# Ethernet.net
KiCad netlist of a schematic drawn in Altium Designer
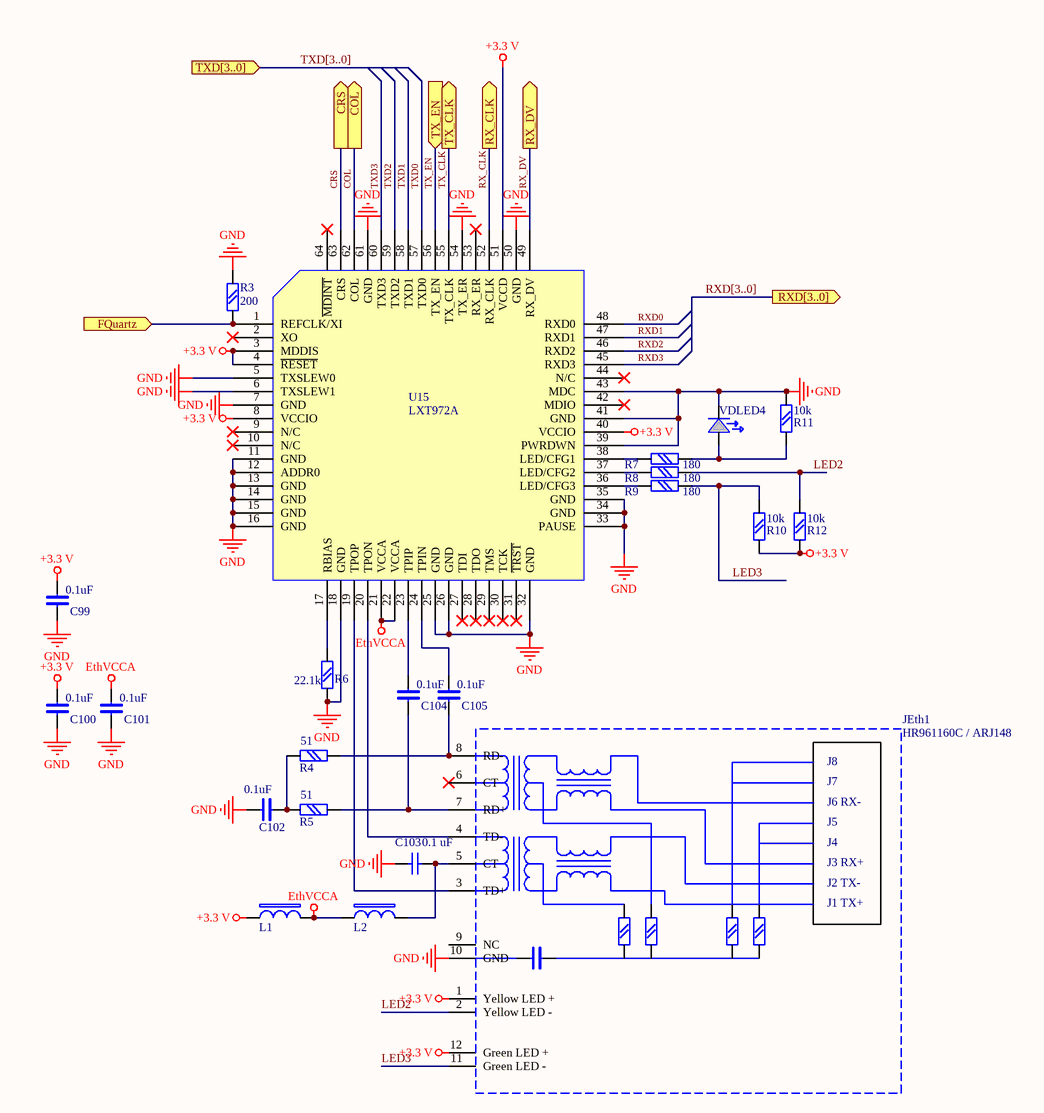
[diagram p0: Ethernet.SchDoc]

(export (version "E")
  (design (tool "Eeschema 10.0.6"))
  (components
    (comp (ref "C99") (value "0.1uF") (footprint "chip0603") (libsource (lib "vDevice") (part "C")))
    (comp (ref "C100") (value "0.1uF") (footprint "chip0603") (libsource (lib "vDevice") (part "C")))
    (comp (ref "C101") (value "0.1uF") (footprint "chip0603") (libsource (lib "vDevice") (part "C")))
    (comp (ref "C102") (value "0.1uF") (footprint "chip0603") (libsource (lib "vDevice") (part "C")))
    (comp (ref "C103")
      (value "0.1 uF")
      (footprint "chip0603")
      (description "Capacitor")
      (fields (field (name "Comment") "0.1uF") (field (name "PUBLISHER") "Altium Limited"))
      (libsource (lib "vDevice") (part "Cap"))
    )
    (comp (ref "C104") (value "0.1uF") (footprint "chip0603") (libsource (lib "vDevice") (part "C")))
    (comp (ref "C105") (value "0.1uF") (footprint "chip0603") (libsource (lib "vDevice") (part "C")))
    (comp (ref "JEth1")
      (value "HR961160C / ARJ148")
      (footprint "HR961160C")
      (libsource (lib "Backup of Mylib") (part "HR961160C"))
    )
    (comp (ref "L1") (value "DR") (footprint "chip0805") (libsource (lib "vDevice") (part "DR")))
    (comp (ref "L2") (value "DR") (footprint "chip0805") (libsource (lib "vDevice") (part "DR")))
    (comp (ref "R3") (value "200") (footprint "chip0603") (libsource (lib "vDevice") (part "R")))
    (comp (ref "R4") (value "51") (footprint "chip0603") (libsource (lib "vDevice") (part "R")))
    (comp (ref "R5") (value "51") (footprint "chip0603") (libsource (lib "vDevice") (part "R")))
    (comp (ref "R6") (value "22.1k") (footprint "chip0603") (libsource (lib "vDevice") (part "R")))
    (comp (ref "R7") (value "180") (footprint "chip0603") (libsource (lib "vDevice") (part "R")))
    (comp (ref "R8") (value "180") (footprint "chip0603") (libsource (lib "vDevice") (part "R")))
    (comp (ref "R9") (value "180") (footprint "chip0603") (libsource (lib "vDevice") (part "R")))
    (comp (ref "R10") (value "10k") (footprint "chip0603") (libsource (lib "vDevice") (part "R")))
    (comp (ref "R11") (value "10k") (footprint "chip0603") (libsource (lib "vDevice") (part "R")))
    (comp (ref "R12") (value "10k") (footprint "chip0603") (libsource (lib "vDevice") (part "R")))
    (comp (ref "U15")
      (value "LXT972A")
      (footprint "TQFP64")
      (libsource (lib "Backup of Mylib") (part "LXT972A"))
    )
    (comp (ref "VDLED4") (value "LED") (footprint "LED2P5_H") (libsource (lib "*") (part "AL307")))
  )
  (nets
    (net (code "1") (name "+3.3 V") (class "Default")
      (node (ref "C100") (pin "2") (pinfunction "2_2") (pintype "passive"))
      (node (ref "C99") (pin "2") (pinfunction "2_2") (pintype "passive"))
      (node (ref "JEth1") (pin "1") (pinfunction "Yellow_LED_+_1") (pintype "passive"))
      (node (ref "JEth1") (pin "12") (pinfunction "Green_LED_+_12") (pintype "passive"))
      (node (ref "L1") (pin "1") (pinfunction "1_1") (pintype "passive"))
      (node (ref "R10") (pin "1") (pinfunction "1_1") (pintype "passive"))
      (node (ref "R12") (pin "1") (pinfunction "1_1") (pintype "passive"))
      (node (ref "U15") (pin "3") (pinfunction "MDDIS_3") (pintype "passive"))
      (node (ref "U15") (pin "4") (pinfunction "RESET_4") (pintype "passive"))
      (node (ref "U15") (pin "40") (pinfunction "VCCIO_40") (pintype "passive"))
      (node (ref "U15") (pin "51") (pinfunction "VCCD_51") (pintype "passive"))
      (node (ref "U15") (pin "8") (pinfunction "VCCIO_8") (pintype "passive"))
    )
    (net (code "2") (name "/COL") (class "Default")
      (node (ref "U15") (pin "62") (pinfunction "COL_62") (pintype "passive"))
    )
    (net (code "3") (name "/CRS") (class "Default")
      (node (ref "U15") (pin "63") (pinfunction "CRS_63") (pintype "passive"))
    )
    (net (code "4") (name "/FQuartz") (class "Default")
      (node (ref "R3") (pin "1") (pinfunction "1_1") (pintype "passive"))
      (node (ref "U15") (pin "1") (pinfunction "REFCLK/XI_1") (pintype "passive"))
    )
    (net (code "5") (name "/LED2") (class "Default")
      (node (ref "JEth1") (pin "2") (pinfunction "Yellow_LED_-_2") (pintype "passive"))
      (node (ref "R12") (pin "2") (pinfunction "2_2") (pintype "passive"))
      (node (ref "R8") (pin "2") (pinfunction "2_2") (pintype "passive"))
    )
    (net (code "6") (name "/LED3") (class "Default")
      (node (ref "JEth1") (pin "11") (pinfunction "Green_LED_-_11") (pintype "passive"))
      (node (ref "R10") (pin "2") (pinfunction "2_2") (pintype "passive"))
      (node (ref "R9") (pin "2") (pinfunction "2_2") (pintype "passive"))
    )
    (net (code "7") (name "/RXD0") (class "Default")
      (node (ref "U15") (pin "48") (pinfunction "RXD0_48") (pintype "passive"))
    )
    (net (code "8") (name "/RXD1") (class "Default")
      (node (ref "U15") (pin "47") (pinfunction "RXD1_47") (pintype "passive"))
    )
    (net (code "9") (name "/RXD2") (class "Default")
      (node (ref "U15") (pin "46") (pinfunction "RXD2_46") (pintype "passive"))
    )
    (net (code "10") (name "/RXD3") (class "Default")
      (node (ref "U15") (pin "45") (pinfunction "RXD3_45") (pintype "passive"))
    )
    (net (code "12") (name "/RX_CLK") (class "Default")
      (node (ref "U15") (pin "52") (pinfunction "RX_CLK_52") (pintype "passive"))
    )
    (net (code "13") (name "/RX_DV") (class "Default")
      (node (ref "U15") (pin "49") (pinfunction "RX_DV_49") (pintype "passive"))
    )
    (net (code "14") (name "/TXD0") (class "Default")
      (node (ref "U15") (pin "57") (pinfunction "TXD0_57") (pintype "passive"))
    )
    (net (code "15") (name "/TXD1") (class "Default")
      (node (ref "U15") (pin "58") (pinfunction "TXD1_58") (pintype "passive"))
    )
    (net (code "16") (name "/TXD2") (class "Default")
      (node (ref "U15") (pin "59") (pinfunction "TXD2_59") (pintype "passive"))
    )
    (net (code "17") (name "/TXD3") (class "Default")
      (node (ref "U15") (pin "60") (pinfunction "TXD3_60") (pintype "passive"))
    )
    (net (code "19") (name "/TX_CLK") (class "Default")
      (node (ref "U15") (pin "55") (pinfunction "TX_CLK_55") (pintype "passive"))
    )
    (net (code "20") (name "/TX_EN") (class "Default")
      (node (ref "U15") (pin "56") (pinfunction "TX_EN_56") (pintype "passive"))
    )
    (net (code "21") (name "EthVCCA") (class "Default")
      (node (ref "C101") (pin "2") (pinfunction "2_2") (pintype "passive"))
      (node (ref "L1") (pin "2") (pinfunction "2_2") (pintype "passive"))
      (node (ref "L2") (pin "1") (pinfunction "1_1") (pintype "passive"))
      (node (ref "U15") (pin "21") (pinfunction "VCCA_21") (pintype "passive"))
      (node (ref "U15") (pin "22") (pinfunction "VCCA_22") (pintype "passive"))
    )
    (net (code "22") (name "GND") (class "Default")
      (node (ref "C100") (pin "1") (pinfunction "1_1") (pintype "passive"))
      (node (ref "C101") (pin "1") (pinfunction "1_1") (pintype "passive"))
      (node (ref "C102") (pin "2") (pinfunction "2_2") (pintype "passive"))
      (node (ref "C103") (pin "1") (pinfunction "1_1") (pintype "passive"))
      (node (ref "C99") (pin "1") (pinfunction "1_1") (pintype "passive"))
      (node (ref "JEth1") (pin "10") (pinfunction "GND_10") (pintype "power_in"))
      (node (ref "R11") (pin "2") (pinfunction "2_2") (pintype "passive"))
      (node (ref "R3") (pin "2") (pinfunction "2_2") (pintype "passive"))
      (node (ref "R6") (pin "2") (pinfunction "2_2") (pintype "passive"))
      (node (ref "U15") (pin "11") (pinfunction "GND_11") (pintype "passive"))
      (node (ref "U15") (pin "12") (pinfunction "ADDR0_12") (pintype "passive"))
      (node (ref "U15") (pin "13") (pinfunction "GND_13") (pintype "passive"))
      (node (ref "U15") (pin "14") (pinfunction "GND_14") (pintype "passive"))
      (node (ref "U15") (pin "15") (pinfunction "GND_15") (pintype "passive"))
      (node (ref "U15") (pin "16") (pinfunction "GND_16") (pintype "passive"))
      (node (ref "U15") (pin "18") (pinfunction "GND_18") (pintype "passive"))
      (node (ref "U15") (pin "25") (pinfunction "GND_25") (pintype "passive"))
      (node (ref "U15") (pin "26") (pinfunction "GND_26") (pintype "passive"))
      (node (ref "U15") (pin "32") (pinfunction "GND_32") (pintype "passive"))
      (node (ref "U15") (pin "33") (pinfunction "PAUSE_33") (pintype "passive"))
      (node (ref "U15") (pin "34") (pinfunction "GND_34") (pintype "passive"))
      (node (ref "U15") (pin "35") (pinfunction "GND_35") (pintype "passive"))
      (node (ref "U15") (pin "39") (pinfunction "PWRDWN_39") (pintype "passive"))
      (node (ref "U15") (pin "41") (pinfunction "GND_41") (pintype "passive"))
      (node (ref "U15") (pin "43") (pinfunction "MDC_43") (pintype "passive"))
      (node (ref "U15") (pin "5") (pinfunction "TXSLEW0_5") (pintype "passive"))
      (node (ref "U15") (pin "50") (pinfunction "GND_50") (pintype "passive"))
      (node (ref "U15") (pin "54") (pinfunction "TX_ER_54") (pintype "passive"))
      (node (ref "U15") (pin "6") (pinfunction "TXSLEW1_6") (pintype "passive"))
      (node (ref "U15") (pin "61") (pinfunction "GND_61") (pintype "passive"))
      (node (ref "U15") (pin "7") (pinfunction "GND_7") (pintype "passive"))
      (node (ref "VDLED4") (pin "CATH") (pinfunction "CATH_CATH") (pintype "passive"))
    )
    (net (code "23") (name "Net-(C102-Pad1)") (class "Default")
      (node (ref "C102") (pin "1") (pinfunction "1_1") (pintype "passive"))
      (node (ref "R4") (pin "1") (pinfunction "1_1") (pintype "passive"))
      (node (ref "R5") (pin "2") (pinfunction "2_2") (pintype "passive"))
    )
    (net (code "24") (name "Net-(C103-Pad2)") (class "Default")
      (node (ref "C103") (pin "2") (pinfunction "2_2") (pintype "passive"))
      (node (ref "JEth1") (pin "5") (pinfunction "CT_5") (pintype "passive"))
      (node (ref "L2") (pin "2") (pinfunction "2_2") (pintype "passive"))
    )
    (net (code "25") (name "Net-(JEth1-RD+)") (class "Default")
      (node (ref "C104") (pin "1") (pinfunction "1_1") (pintype "passive"))
      (node (ref "JEth1") (pin "7") (pinfunction "RD+_7") (pintype "passive"))
      (node (ref "R5") (pin "1") (pinfunction "1_1") (pintype "passive"))
    )
    (net (code "26") (name "Net-(JEth1-RD-)") (class "Default")
      (node (ref "C105") (pin "1") (pinfunction "1_1") (pintype "passive"))
      (node (ref "JEth1") (pin "8") (pinfunction "RD-_8") (pintype "passive"))
      (node (ref "R4") (pin "2") (pinfunction "2_2") (pintype "passive"))
    )
    (net (code "27") (name "Net-(JEth1-TD+)") (class "Default")
      (node (ref "JEth1") (pin "3") (pinfunction "TD+_3") (pintype "passive"))
      (node (ref "U15") (pin "19") (pinfunction "TPOP_19") (pintype "passive"))
    )
    (net (code "28") (name "Net-(JEth1-TD-)") (class "Default")
      (node (ref "JEth1") (pin "4") (pinfunction "TD-_4") (pintype "passive"))
      (node (ref "U15") (pin "20") (pinfunction "TPON_20") (pintype "passive"))
    )
    (net (code "29") (name "Net-(R11-Pad1)") (class "Default")
      (node (ref "R11") (pin "1") (pinfunction "1_1") (pintype "passive"))
      (node (ref "R7") (pin "2") (pinfunction "2_2") (pintype "passive"))
      (node (ref "VDLED4") (pin "ANOD") (pinfunction "ANOD_ANOD") (pintype "passive"))
    )
    (net (code "30") (name "Net-(U15-LED{slash}CFG1)") (class "Default")
      (node (ref "R7") (pin "1") (pinfunction "1_1") (pintype "passive"))
      (node (ref "U15") (pin "38") (pinfunction "LED/CFG1_38") (pintype "passive"))
    )
    (net (code "31") (name "Net-(U15-LED{slash}CFG2)") (class "Default")
      (node (ref "R8") (pin "1") (pinfunction "1_1") (pintype "passive"))
      (node (ref "U15") (pin "37") (pinfunction "LED/CFG2_37") (pintype "passive"))
    )
    (net (code "32") (name "Net-(U15-LED{slash}CFG3)") (class "Default")
      (node (ref "R9") (pin "1") (pinfunction "1_1") (pintype "passive"))
      (node (ref "U15") (pin "36") (pinfunction "LED/CFG3_36") (pintype "passive"))
    )
    (net (code "33") (name "Net-(U15-RBIAS)") (class "Default")
      (node (ref "R6") (pin "1") (pinfunction "1_1") (pintype "passive"))
      (node (ref "U15") (pin "17") (pinfunction "RBIAS_17") (pintype "passive"))
    )
    (net (code "34") (name "Net-(U15-TPIN)") (class "Default")
      (node (ref "C105") (pin "2") (pinfunction "2_2") (pintype "passive"))
      (node (ref "U15") (pin "24") (pinfunction "TPIN_24") (pintype "passive"))
    )
    (net (code "35") (name "Net-(U15-TPIP)") (class "Default")
      (node (ref "C104") (pin "2") (pinfunction "2_2") (pintype "passive"))
      (node (ref "U15") (pin "23") (pinfunction "TPIP_23") (pintype "passive"))
    )
    (net (code "36") (name "unconnected-(JEth1-CT-Pad6)") (class "Default")
      (node (ref "JEth1") (pin "6") (pinfunction "CT_6") (pintype "passive+no_connect"))
    )
    (net (code "37") (name "unconnected-(JEth1-NC-Pad9)") (class "Default")
      (node (ref "JEth1") (pin "9") (pinfunction "NC_9") (pintype "passive"))
    )
    (net (code "38") (name "unconnected-(JEth1-Pad1)") (class "Default")
      (node (ref "JEth1") (pin "1") (pinfunction "1_1") (pintype "passive"))
    )
    (net (code "39") (name "unconnected-(JEth1-Pad1)_1") (class "Default")
      (node (ref "JEth1") (pin "1") (pinfunction "1_1") (pintype "passive"))
    )
    (net (code "40") (name "unconnected-(JEth1-Pad1)_2") (class "Default")
      (node (ref "JEth1") (pin "1") (pinfunction "1_1") (pintype "passive"))
    )
    (net (code "41") (name "unconnected-(JEth1-Pad1)_3") (class "Default")
      (node (ref "JEth1") (pin "1") (pinfunction "1_1") (pintype "passive"))
    )
    (net (code "42") (name "unconnected-(JEth1-Pad1)_4") (class "Default")
      (node (ref "JEth1") (pin "1") (pinfunction "1_1") (pintype "passive"))
    )
    (net (code "43") (name "unconnected-(JEth1-Pad2)") (class "Default")
      (node (ref "JEth1") (pin "2") (pinfunction "2_2") (pintype "passive"))
    )
    (net (code "44") (name "unconnected-(JEth1-Pad2)_1") (class "Default")
      (node (ref "JEth1") (pin "2") (pinfunction "2_2") (pintype "passive"))
    )
    (net (code "45") (name "unconnected-(JEth1-Pad2)_2") (class "Default")
      (node (ref "JEth1") (pin "2") (pinfunction "2_2") (pintype "passive"))
    )
    (net (code "46") (name "unconnected-(JEth1-Pad2)_3") (class "Default")
      (node (ref "JEth1") (pin "2") (pinfunction "2_2") (pintype "passive"))
    )
    (net (code "47") (name "unconnected-(JEth1-Pad2)_4") (class "Default")
      (node (ref "JEth1") (pin "2") (pinfunction "2_2") (pintype "passive"))
    )
    (net (code "48") (name "unconnected-(U15-MDINT-Pad64)") (class "Default")
      (node (ref "U15") (pin "64") (pinfunction "MDINT_64") (pintype "passive+no_connect"))
    )
    (net (code "49") (name "unconnected-(U15-MDIO-Pad42)") (class "Default")
      (node (ref "U15") (pin "42") (pinfunction "MDIO_42") (pintype "passive+no_connect"))
    )
    (net (code "50") (name "unconnected-(U15-N{slash}C-Pad9)") (class "Default")
      (node (ref "U15") (pin "9") (pinfunction "N/C_9") (pintype "passive+no_connect"))
    )
    (net (code "51") (name "unconnected-(U15-N{slash}C-Pad10)") (class "Default")
      (node (ref "U15") (pin "10") (pinfunction "N/C_10") (pintype "passive+no_connect"))
    )
    (net (code "52") (name "unconnected-(U15-N{slash}C-Pad44)") (class "Default")
      (node (ref "U15") (pin "44") (pinfunction "N/C_44") (pintype "passive+no_connect"))
    )
    (net (code "53") (name "unconnected-(U15-RX_ER-Pad53)") (class "Default")
      (node (ref "U15") (pin "53") (pinfunction "RX_ER_53") (pintype "passive+no_connect"))
    )
    (net (code "54") (name "unconnected-(U15-TCK-Pad30)") (class "Default")
      (node (ref "U15") (pin "30") (pinfunction "TCK_30") (pintype "passive+no_connect"))
    )
    (net (code "55") (name "unconnected-(U15-TDI-Pad27)") (class "Default")
      (node (ref "U15") (pin "27") (pinfunction "TDI_27") (pintype "passive+no_connect"))
    )
    (net (code "56") (name "unconnected-(U15-TDO-Pad28)") (class "Default")
      (node (ref "U15") (pin "28") (pinfunction "TDO_28") (pintype "passive+no_connect"))
    )
    (net (code "57") (name "unconnected-(U15-TMS-Pad29)") (class "Default")
      (node (ref "U15") (pin "29") (pinfunction "TMS_29") (pintype "passive+no_connect"))
    )
    (net (code "58") (name "unconnected-(U15-TRST-Pad31)") (class "Default")
      (node (ref "U15") (pin "31") (pinfunction "TRST_31") (pintype "passive+no_connect"))
    )
    (net (code "59") (name "unconnected-(U15-XO-Pad2)") (class "Default")
      (node (ref "U15") (pin "2") (pinfunction "XO_2") (pintype "passive+no_connect"))
    )
  )
)
